# BMS_Carrier_-_Connectors.net
KiCad netlist of a schematic drawn in Altium Designer
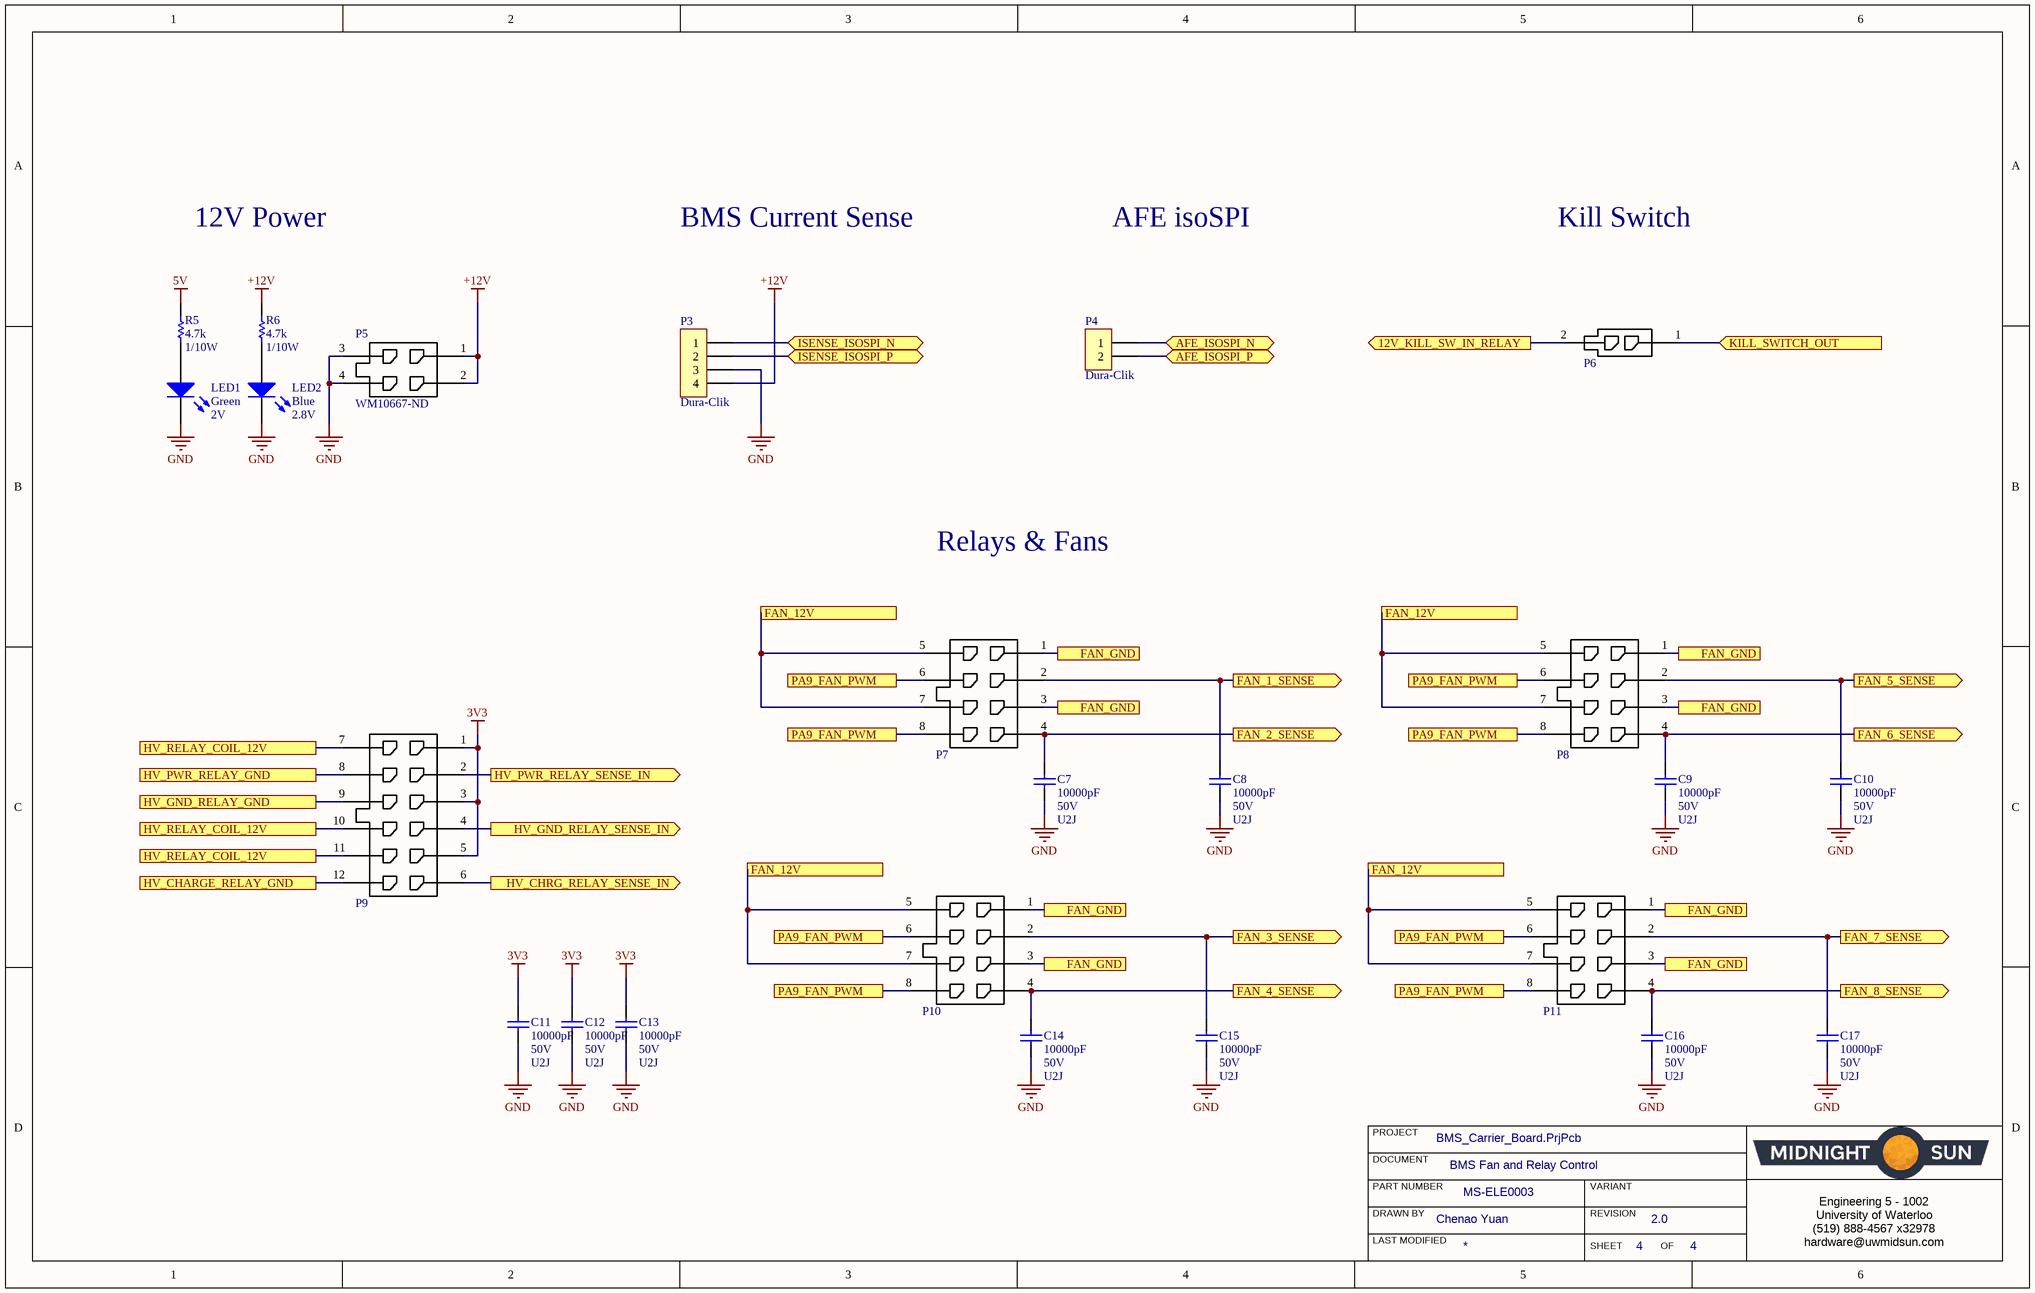
[diagram p0: BMS Carrier - Connectors.SchDoc]

(export (version "E")
  (design (tool "Eeschema 10.0.6"))
  (components
    (comp (ref "C7")
      (value "CAP CER 10nF 50V 5% X7R 0603")
      (footprint "CAP, 0603")
      (description "10000pF ±5% 50V Ceramic Capacitor U2J 0603 (1608 Metric)")
      (fields
        (field (name "TOLERANCE") "±5%")
        (field (name "CAPACITANCE") "10000pF")
        (field (name "VOLTAGE") "50V")
        (field (name "TEMPERATURE COEFFICIENT") "U2J")
      )
      (libsource (lib "Schematic Diagrams") (part "CAP CER 10nF 50V 5% X7R 0603"))
    )
    (comp (ref "C8")
      (value "CAP CER 10nF 50V 5% X7R 0603")
      (footprint "CAP, 0603")
      (description "10000pF ±5% 50V Ceramic Capacitor U2J 0603 (1608 Metric)")
      (fields
        (field (name "TOLERANCE") "±5%")
        (field (name "CAPACITANCE") "10000pF")
        (field (name "VOLTAGE") "50V")
        (field (name "TEMPERATURE COEFFICIENT") "U2J")
      )
      (libsource (lib "Schematic Diagrams") (part "CAP CER 10nF 50V 5% X7R 0603"))
    )
    (comp (ref "C9")
      (value "CAP CER 10nF 50V 5% X7R 0603")
      (footprint "CAP, 0603")
      (description "10000pF ±5% 50V Ceramic Capacitor U2J 0603 (1608 Metric)")
      (fields
        (field (name "TOLERANCE") "±5%")
        (field (name "CAPACITANCE") "10000pF")
        (field (name "VOLTAGE") "50V")
        (field (name "TEMPERATURE COEFFICIENT") "U2J")
      )
      (libsource (lib "Schematic Diagrams") (part "CAP CER 10nF 50V 5% X7R 0603"))
    )
    (comp (ref "C10")
      (value "CAP CER 10nF 50V 5% X7R 0603")
      (footprint "CAP, 0603")
      (description "10000pF ±5% 50V Ceramic Capacitor U2J 0603 (1608 Metric)")
      (fields
        (field (name "TOLERANCE") "±5%")
        (field (name "CAPACITANCE") "10000pF")
        (field (name "VOLTAGE") "50V")
        (field (name "TEMPERATURE COEFFICIENT") "U2J")
      )
      (libsource (lib "Schematic Diagrams") (part "CAP CER 10nF 50V 5% X7R 0603"))
    )
    (comp (ref "C11")
      (value "CAP CER 10nF 50V 5% X7R 0603")
      (footprint "CAP, 0603")
      (description "10000pF ±5% 50V Ceramic Capacitor U2J 0603 (1608 Metric)")
      (fields
        (field (name "TOLERANCE") "±5%")
        (field (name "CAPACITANCE") "10000pF")
        (field (name "VOLTAGE") "50V")
        (field (name "TEMPERATURE COEFFICIENT") "U2J")
      )
      (libsource (lib "Schematic Diagrams") (part "CAP CER 10nF 50V 5% X7R 0603"))
    )
    (comp (ref "C12")
      (value "CAP CER 10nF 50V 5% X7R 0603")
      (footprint "CAP, 0603")
      (description "10000pF ±5% 50V Ceramic Capacitor U2J 0603 (1608 Metric)")
      (fields
        (field (name "TOLERANCE") "±5%")
        (field (name "CAPACITANCE") "10000pF")
        (field (name "VOLTAGE") "50V")
        (field (name "TEMPERATURE COEFFICIENT") "U2J")
      )
      (libsource (lib "Schematic Diagrams") (part "CAP CER 10nF 50V 5% X7R 0603"))
    )
    (comp (ref "C13")
      (value "CAP CER 10nF 50V 5% X7R 0603")
      (footprint "CAP, 0603")
      (description "10000pF ±5% 50V Ceramic Capacitor U2J 0603 (1608 Metric)")
      (fields
        (field (name "TOLERANCE") "±5%")
        (field (name "CAPACITANCE") "10000pF")
        (field (name "VOLTAGE") "50V")
        (field (name "TEMPERATURE COEFFICIENT") "U2J")
      )
      (libsource (lib "Schematic Diagrams") (part "CAP CER 10nF 50V 5% X7R 0603"))
    )
    (comp (ref "C14")
      (value "CAP CER 10nF 50V 5% X7R 0603")
      (footprint "CAP, 0603")
      (description "10000pF ±5% 50V Ceramic Capacitor U2J 0603 (1608 Metric)")
      (fields
        (field (name "TOLERANCE") "±5%")
        (field (name "CAPACITANCE") "10000pF")
        (field (name "VOLTAGE") "50V")
        (field (name "TEMPERATURE COEFFICIENT") "U2J")
      )
      (libsource (lib "Schematic Diagrams") (part "CAP CER 10nF 50V 5% X7R 0603"))
    )
    (comp (ref "C15")
      (value "CAP CER 10nF 50V 5% X7R 0603")
      (footprint "CAP, 0603")
      (description "10000pF ±5% 50V Ceramic Capacitor U2J 0603 (1608 Metric)")
      (fields
        (field (name "TOLERANCE") "±5%")
        (field (name "CAPACITANCE") "10000pF")
        (field (name "VOLTAGE") "50V")
        (field (name "TEMPERATURE COEFFICIENT") "U2J")
      )
      (libsource (lib "Schematic Diagrams") (part "CAP CER 10nF 50V 5% X7R 0603"))
    )
    (comp (ref "C16")
      (value "CAP CER 10nF 50V 5% X7R 0603")
      (footprint "CAP, 0603")
      (description "10000pF ±5% 50V Ceramic Capacitor U2J 0603 (1608 Metric)")
      (fields
        (field (name "TOLERANCE") "±5%")
        (field (name "CAPACITANCE") "10000pF")
        (field (name "VOLTAGE") "50V")
        (field (name "TEMPERATURE COEFFICIENT") "U2J")
      )
      (libsource (lib "Schematic Diagrams") (part "CAP CER 10nF 50V 5% X7R 0603"))
    )
    (comp (ref "C17")
      (value "CAP CER 10nF 50V 5% X7R 0603")
      (footprint "CAP, 0603")
      (description "10000pF ±5% 50V Ceramic Capacitor U2J 0603 (1608 Metric)")
      (fields
        (field (name "TOLERANCE") "±5%")
        (field (name "CAPACITANCE") "10000pF")
        (field (name "VOLTAGE") "50V")
        (field (name "TEMPERATURE COEFFICIENT") "U2J")
      )
      (libsource (lib "Schematic Diagrams") (part "CAP CER 10nF 50V 5% X7R 0603"))
    )
    (comp (ref "LED1")
      (value "LED GREEN CLEAR 2V 0603")
      (footprint "LED_0603")
      (description "Green 572nm LED Indication - Discrete 2V 0603 (1608 Metric)")
      (fields
        (field (name "MANUFACTURER") "Wurth Electronics Inc.")
        (field (name "MANUFACTURER PART NUMBER") "150060VS75000")
        (field (name "COLOR") "Green")
        (field (name "VOLTAGE - FORWARD (VF) (TYP)") "2V")
      )
      (libsource (lib "Schematic Diagrams") (part "LED GREEN CLEAR 2V 0603"))
    )
    (comp (ref "LED2")
      (value "LED BLUE CLEAR 2.8V 0603")
      (footprint "LED_0603")
      (description "Blue 470nm LED Indication - Discrete 2.8V 0603 (1608 Metric)")
      (fields (field (name "COLOR") "Blue") (field (name "VOLTAGE - FORWARD (VF) (TYP)") "2.8V"))
      (libsource (lib "Schematic Diagrams") (part "LED BLUE CLEAR 2.8V 0603"))
    )
    (comp (ref "P3")
      (value "Dura-Clik")
      (footprint "CONN, 4POS DURA-CLIK VERT")
      (description "4 Positions Header Connector 0.079\" (2.00mm) Surface Mount Tin")
      (fields
        (field (name "MANUFACTURER") "Molex, LLC")
        (field (name "MANUFACTURER PART NUMBER") "5600200420")
      )
      (libsource (lib "Schematic Diagrams") (part "CONN 4POS DURA-CLIK 0.079{dblquote}"))
    )
    (comp (ref "P4")
      (value "Dura-Clik")
      (footprint "CONN, 2POS Dura-Click Vertical")
      (description "2 Positions Header, Shrouded Connector 0.079\" (2.00mm) Surface Mount, Vertical Tin")
      (fields
        (field (name "MANUFACTURER") "Molex, LLC")
        (field (name "MANUFACTURER PART NUMBER") "5600200220")
      )
      (libsource (lib "Schematic Diagrams") (part "CONN 2POS DURA-CLIK 0.079{dblquote} VERT"))
    )
    (comp (ref "P5")
      (value "CONN 4POS MICRO-FIT 3mm")
      (footprint "CONN, 4POS MICRO-FIT")
      (fields
        (field (name "MANUFACTURER") "Molex, LLC")
        (field (name "MANUFACTURER PART NUMBER") "0430450827")
        (field (name "SUPPLIER PART NUMBER 1") "WM10667-ND")
      )
      (libsource (lib "Schematic Diagrams") (part "CONN 4POS MICRO-FIT 3mm"))
    )
    (comp (ref "P6")
      (value "CONN 2POS MICRO-FIT 3mm")
      (footprint "CONN, 2POS MICRO-FIT")
      (description "Connector Header Through Hole 2 position")
      (fields (field (name "MANUFACTURER") "Molex") (field (name "MANUFACTURER PART NUMBER") "43045-0227"))
      (libsource (lib "Schematic Diagrams") (part "CONN 2POS MICRO-FIT 3mm"))
    )
    (comp (ref "P7")
      (value "CONN 8POS MICRO-FIT 3mm")
      (footprint "CONN, 8POS MICRO-FIT")
      (description "Connector Header Through Hole 6 position 0.118\" (3.00mm)")
      (fields
        (field (name "MANUFACTURER") "Molex, LLC")
        (field (name "MANUFACTURER PART NUMBER") "0430450827")
      )
      (libsource (lib "Schematic Diagrams") (part "CONN 8POS MICRO-FIT 3mm"))
    )
    (comp (ref "P8")
      (value "CONN 8POS MICRO-FIT 3mm")
      (footprint "CONN, 8POS MICRO-FIT")
      (description "Connector Header Through Hole 6 position 0.118\" (3.00mm)")
      (fields
        (field (name "MANUFACTURER") "Molex, LLC")
        (field (name "MANUFACTURER PART NUMBER") "0430450827")
      )
      (libsource (lib "Schematic Diagrams") (part "CONN 8POS MICRO-FIT 3mm"))
    )
    (comp (ref "P9")
      (value "CONN 12POS MICRO-FIT 3mm")
      (footprint "CONN, 12POS MICRO-FIT 3mm")
      (description "Connector Header Through Hole 12 position 0.118\" (3.00mm)")
      (fields
        (field (name "MANUFACTURER") "Molex, LLC")
        (field (name "MANUFACTURER PART NUMBER") "0430451227")
      )
      (libsource (lib "Schematic Diagrams") (part "CONN 12POS MICRO-FIT 3mm"))
    )
    (comp (ref "P10")
      (value "CONN 8POS MICRO-FIT 3mm")
      (footprint "CONN, 8POS MICRO-FIT")
      (description "Connector Header Through Hole 6 position 0.118\" (3.00mm)")
      (fields
        (field (name "MANUFACTURER") "Molex, LLC")
        (field (name "MANUFACTURER PART NUMBER") "0430450827")
      )
      (libsource (lib "Schematic Diagrams") (part "CONN 8POS MICRO-FIT 3mm"))
    )
    (comp (ref "P11")
      (value "CONN 8POS MICRO-FIT 3mm")
      (footprint "CONN, 8POS MICRO-FIT")
      (description "Connector Header Through Hole 6 position 0.118\" (3.00mm)")
      (fields
        (field (name "MANUFACTURER") "Molex, LLC")
        (field (name "MANUFACTURER PART NUMBER") "0430450827")
      )
      (libsource (lib "Schematic Diagrams") (part "CONN 8POS MICRO-FIT 3mm"))
    )
    (comp (ref "R5")
      (value "RES 4.7K OHM 1% 1/10W 0603")
      (footprint "RES, 0603")
      (description "4.7k Ohm ±1% 0.1W, 1/10W Chip Resistor 0603 (1608 Metric) Moisture Resistant Thick Film")
      (fields
        (field (name "TOLERANCE") "±1%")
        (field (name "RESISTANCE (OHMS)") "4.7k")
        (field (name "POWER (WATTS)") "1/10W")
      )
      (libsource (lib "Schematic Diagrams") (part "RES 4.7K OHM 1% 1/10W 0603"))
    )
    (comp (ref "R6")
      (value "RES 4.7K OHM 1% 1/10W 0603")
      (footprint "RES, 0603")
      (description "4.7k Ohm ±1% 0.1W, 1/10W Chip Resistor 0603 (1608 Metric) Moisture Resistant Thick Film")
      (fields
        (field (name "TOLERANCE") "±1%")
        (field (name "RESISTANCE (OHMS)") "4.7k")
        (field (name "POWER (WATTS)") "1/10W")
      )
      (libsource (lib "Schematic Diagrams") (part "RES 4.7K OHM 1% 1/10W 0603"))
    )
  )
  (nets
    (net (code "1") (name "+12V") (class "Default")
      (node (ref "P3") (pin "4") (pinfunction "4_4") (pintype "passive"))
      (node (ref "P5") (pin "1") (pinfunction "1_1") (pintype "passive"))
      (node (ref "P5") (pin "2") (pinfunction "2_2") (pintype "passive"))
      (node (ref "R6") (pin "1") (pinfunction "1_1") (pintype "passive"))
    )
    (net (code "2") (name "/12V_KILL_SW_IN_RELAY") (class "Default")
      (node (ref "P6") (pin "2") (pinfunction "2_2") (pintype "passive"))
    )
    (net (code "3") (name "/AFE_ISOSPI_N") (class "Default")
      (node (ref "P4") (pin "1") (pinfunction "1_1") (pintype "passive"))
    )
    (net (code "4") (name "/AFE_ISOSPI_P") (class "Default")
      (node (ref "P4") (pin "2") (pinfunction "2_2") (pintype "passive"))
    )
    (net (code "5") (name "/FAN_1_SENSE") (class "Default")
      (node (ref "C8") (pin "1") (pinfunction "1_1") (pintype "passive"))
      (node (ref "P7") (pin "2") (pinfunction "2_2") (pintype "passive"))
    )
    (net (code "6") (name "/FAN_2_SENSE") (class "Default")
      (node (ref "C7") (pin "1") (pinfunction "1_1") (pintype "passive"))
      (node (ref "P7") (pin "4") (pinfunction "4_4") (pintype "passive"))
    )
    (net (code "7") (name "/FAN_3_SENSE") (class "Default")
      (node (ref "C15") (pin "1") (pinfunction "1_1") (pintype "passive"))
      (node (ref "P10") (pin "2") (pinfunction "2_2") (pintype "passive"))
    )
    (net (code "8") (name "/FAN_4_SENSE") (class "Default")
      (node (ref "C14") (pin "1") (pinfunction "1_1") (pintype "passive"))
      (node (ref "P10") (pin "4") (pinfunction "4_4") (pintype "passive"))
    )
    (net (code "9") (name "/FAN_5_SENSE") (class "Default")
      (node (ref "C10") (pin "1") (pinfunction "1_1") (pintype "passive"))
      (node (ref "P8") (pin "2") (pinfunction "2_2") (pintype "passive"))
    )
    (net (code "10") (name "/FAN_6_SENSE") (class "Default")
      (node (ref "C9") (pin "1") (pinfunction "1_1") (pintype "passive"))
      (node (ref "P8") (pin "4") (pinfunction "4_4") (pintype "passive"))
    )
    (net (code "11") (name "/FAN_7_SENSE") (class "Default")
      (node (ref "C17") (pin "1") (pinfunction "1_1") (pintype "passive"))
      (node (ref "P11") (pin "2") (pinfunction "2_2") (pintype "passive"))
    )
    (net (code "12") (name "/FAN_8_SENSE") (class "Default")
      (node (ref "C16") (pin "1") (pinfunction "1_1") (pintype "passive"))
      (node (ref "P11") (pin "4") (pinfunction "4_4") (pintype "passive"))
    )
    (net (code "13") (name "/FAN_12V") (class "Default")
      (node (ref "P10") (pin "5") (pinfunction "5_5") (pintype "passive"))
      (node (ref "P10") (pin "7") (pinfunction "7_7") (pintype "passive"))
      (node (ref "P11") (pin "5") (pinfunction "5_5") (pintype "passive"))
      (node (ref "P11") (pin "7") (pinfunction "7_7") (pintype "passive"))
      (node (ref "P7") (pin "5") (pinfunction "5_5") (pintype "passive"))
      (node (ref "P7") (pin "7") (pinfunction "7_7") (pintype "passive"))
      (node (ref "P8") (pin "5") (pinfunction "5_5") (pintype "passive"))
      (node (ref "P8") (pin "7") (pinfunction "7_7") (pintype "passive"))
    )
    (net (code "14") (name "/FAN_GND") (class "Default")
      (node (ref "P10") (pin "1") (pinfunction "1_1") (pintype "passive"))
      (node (ref "P10") (pin "3") (pinfunction "3_3") (pintype "passive"))
      (node (ref "P11") (pin "1") (pinfunction "1_1") (pintype "passive"))
      (node (ref "P11") (pin "3") (pinfunction "3_3") (pintype "passive"))
      (node (ref "P7") (pin "1") (pinfunction "1_1") (pintype "passive"))
      (node (ref "P7") (pin "3") (pinfunction "3_3") (pintype "passive"))
      (node (ref "P8") (pin "1") (pinfunction "1_1") (pintype "passive"))
      (node (ref "P8") (pin "3") (pinfunction "3_3") (pintype "passive"))
    )
    (net (code "15") (name "/HV_CHARGE_RELAY_GND") (class "Default")
      (node (ref "P9") (pin "12") (pinfunction "12_12") (pintype "passive"))
    )
    (net (code "16") (name "/HV_CHRG_RELAY_SENSE_IN") (class "Default")
      (node (ref "P9") (pin "6") (pinfunction "6_6") (pintype "passive"))
    )
    (net (code "17") (name "/HV_GND_RELAY_GND") (class "Default")
      (node (ref "P9") (pin "9") (pinfunction "9_9") (pintype "passive"))
    )
    (net (code "18") (name "/HV_GND_RELAY_SENSE_IN") (class "Default")
      (node (ref "P9") (pin "4") (pinfunction "4_4") (pintype "passive"))
    )
    (net (code "19") (name "/HV_PWR_RELAY_GND") (class "Default")
      (node (ref "P9") (pin "8") (pinfunction "8_8") (pintype "passive"))
    )
    (net (code "20") (name "/HV_PWR_RELAY_SENSE_IN") (class "Default")
      (node (ref "P9") (pin "2") (pinfunction "2_2") (pintype "passive"))
    )
    (net (code "21") (name "/HV_RELAY_COIL_12V") (class "Default")
      (node (ref "P9") (pin "10") (pinfunction "10_10") (pintype "passive"))
      (node (ref "P9") (pin "11") (pinfunction "11_11") (pintype "passive"))
      (node (ref "P9") (pin "7") (pinfunction "7_7") (pintype "passive"))
    )
    (net (code "22") (name "/ISENSE_ISOSPI_N") (class "Default")
      (node (ref "P3") (pin "1") (pinfunction "1_1") (pintype "passive"))
    )
    (net (code "23") (name "/ISENSE_ISOSPI_P") (class "Default")
      (node (ref "P3") (pin "2") (pinfunction "2_2") (pintype "passive"))
    )
    (net (code "24") (name "/KILL_SWITCH_OUT") (class "Default")
      (node (ref "P6") (pin "1") (pinfunction "1_1") (pintype "passive"))
    )
    (net (code "25") (name "/PA9_FAN_PWM") (class "Default")
      (node (ref "P10") (pin "6") (pinfunction "6_6") (pintype "passive"))
      (node (ref "P10") (pin "8") (pinfunction "8_8") (pintype "passive"))
      (node (ref "P11") (pin "6") (pinfunction "6_6") (pintype "passive"))
      (node (ref "P11") (pin "8") (pinfunction "8_8") (pintype "passive"))
      (node (ref "P7") (pin "6") (pinfunction "6_6") (pintype "passive"))
      (node (ref "P7") (pin "8") (pinfunction "8_8") (pintype "passive"))
      (node (ref "P8") (pin "6") (pinfunction "6_6") (pintype "passive"))
      (node (ref "P8") (pin "8") (pinfunction "8_8") (pintype "passive"))
    )
    (net (code "26") (name "3V3") (class "Default")
      (node (ref "C11") (pin "1") (pinfunction "1_1") (pintype "passive"))
      (node (ref "C12") (pin "1") (pinfunction "1_1") (pintype "passive"))
      (node (ref "C13") (pin "1") (pinfunction "1_1") (pintype "passive"))
      (node (ref "P9") (pin "1") (pinfunction "1_1") (pintype "passive"))
      (node (ref "P9") (pin "3") (pinfunction "3_3") (pintype "passive"))
      (node (ref "P9") (pin "5") (pinfunction "5_5") (pintype "passive"))
    )
    (net (code "27") (name "5V") (class "Default")
      (node (ref "R5") (pin "1") (pinfunction "1_1") (pintype "passive"))
    )
    (net (code "28") (name "GND") (class "Default")
      (node (ref "C10") (pin "2") (pinfunction "2_2") (pintype "passive"))
      (node (ref "C11") (pin "2") (pinfunction "2_2") (pintype "passive"))
      (node (ref "C12") (pin "2") (pinfunction "2_2") (pintype "passive"))
      (node (ref "C13") (pin "2") (pinfunction "2_2") (pintype "passive"))
      (node (ref "C14") (pin "2") (pinfunction "2_2") (pintype "passive"))
      (node (ref "C15") (pin "2") (pinfunction "2_2") (pintype "passive"))
      (node (ref "C16") (pin "2") (pinfunction "2_2") (pintype "passive"))
      (node (ref "C17") (pin "2") (pinfunction "2_2") (pintype "passive"))
      (node (ref "C7") (pin "2") (pinfunction "2_2") (pintype "passive"))
      (node (ref "C8") (pin "2") (pinfunction "2_2") (pintype "passive"))
      (node (ref "C9") (pin "2") (pinfunction "2_2") (pintype "passive"))
      (node (ref "LED1") (pin "2") (pinfunction "K_2") (pintype "passive"))
      (node (ref "LED2") (pin "2") (pinfunction "K_2") (pintype "passive"))
      (node (ref "P3") (pin "3") (pinfunction "3_3") (pintype "passive"))
      (node (ref "P5") (pin "3") (pinfunction "3_3") (pintype "passive"))
      (node (ref "P5") (pin "4") (pinfunction "4_4") (pintype "passive"))
    )
    (net (code "29") (name "Net-(LED1-A)") (class "Default")
      (node (ref "LED1") (pin "1") (pinfunction "A_1") (pintype "passive"))
      (node (ref "R5") (pin "2") (pinfunction "2_2") (pintype "passive"))
    )
    (net (code "30") (name "Net-(LED2-A)") (class "Default")
      (node (ref "LED2") (pin "1") (pinfunction "A_1") (pintype "passive"))
      (node (ref "R6") (pin "2") (pinfunction "2_2") (pintype "passive"))
    )
  )
)
